# USB.net
KiCad netlist of a schematic drawn in Altium Designer
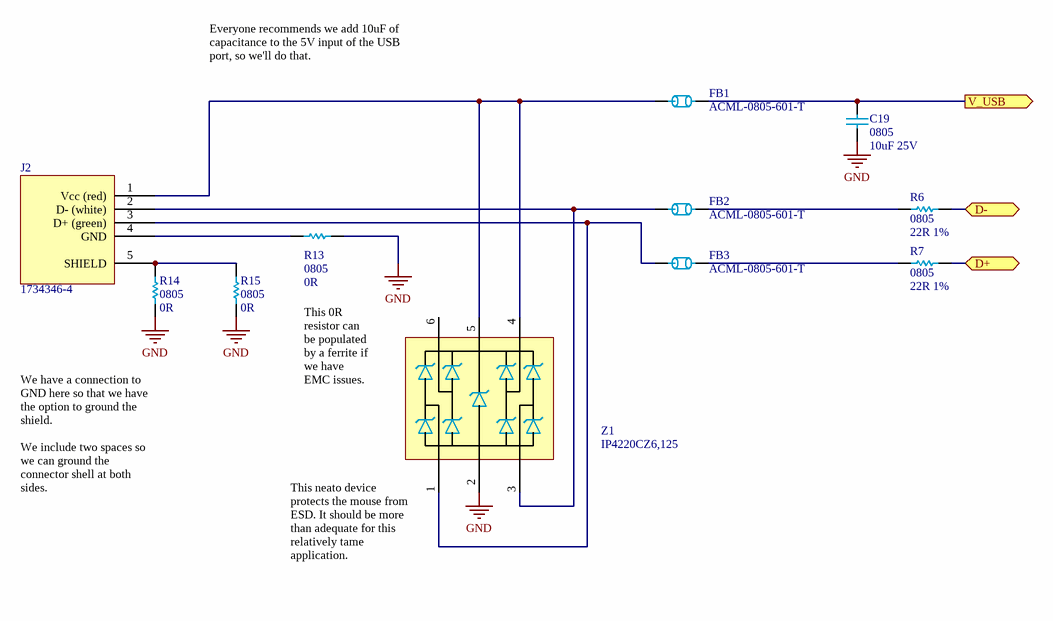
[diagram p0: USB.SchDoc]

(export (version "E")
  (design (tool "Eeschema 10.0.6"))
  (components
    (comp (ref "C19")
      (value "0805")
      (footprint "0805")
      (description "0805, X5R or better")
      (fields (field (name "ALTIUM_VALUE") "10uF 25V"))
      (libsource (lib "Chip_Passives") (part "Cap 10uF 25V"))
    )
    (comp (ref "FB1")
      (value "ACML-0805-601-T")
      (footprint "0805")
      (description "FERRITE BEAD 600 OHM 0805 1LN")
      (libsource (lib "Chip_Passives") (part "ACML-0805-601-T"))
    )
    (comp (ref "FB2")
      (value "ACML-0805-601-T")
      (footprint "0805")
      (description "FERRITE BEAD 600 OHM 0805 1LN")
      (libsource (lib "Chip_Passives") (part "ACML-0805-601-T"))
    )
    (comp (ref "FB3")
      (value "ACML-0805-601-T")
      (footprint "0805")
      (description "FERRITE BEAD 600 OHM 0805 1LN")
      (libsource (lib "Chip_Passives") (part "ACML-0805-601-T"))
    )
    (comp (ref "J2")
      (value "1734346-4")
      (footprint "1734346-4")
      (description "USB - B USB 2.0 Receptacle Connector 4 Position Surface Mount, Right Angle")
      (libsource (lib "Connectors") (part "1734346-4"))
    )
    (comp (ref "R6")
      (value "0805")
      (footprint "0805")
      (description "Chip resistor")
      (fields (field (name "ALTIUM_VALUE") "22R 1%"))
      (libsource (lib "Chip_Passives") (part "Res 22R 1% 0805"))
    )
    (comp (ref "R7")
      (value "0805")
      (footprint "0805")
      (description "Chip resistor")
      (fields (field (name "ALTIUM_VALUE") "22R 1%"))
      (libsource (lib "Chip_Passives") (part "Res 22R 1% 0805"))
    )
    (comp (ref "R13")
      (value "0805")
      (footprint "0805")
      (description "Chip resistor")
      (fields (field (name "ALTIUM_VALUE") "0R"))
      (libsource (lib "Chip_Passives") (part "Res 0R 0805"))
    )
    (comp (ref "R14")
      (value "0805")
      (footprint "0805")
      (description "Chip resistor")
      (fields (field (name "ALTIUM_VALUE") "0R"))
      (libsource (lib "Chip_Passives") (part "Res 0R 0805"))
    )
    (comp (ref "R15")
      (value "0805")
      (footprint "0805")
      (description "Chip resistor")
      (fields (field (name "ALTIUM_VALUE") "0R"))
      (libsource (lib "Chip_Passives") (part "Res 0R 0805"))
    )
    (comp (ref "Z1")
      (value "IP4220CZ6,125")
      (footprint "PESD3V3S4UD - SOT95P275X110-6N")
      (description "TVS DIODE 5.5V 6TSOP (Low capacitance, USB)")
      (libsource (lib "Diodes") (part "IP4220CZ6,125"))
    )
  )
  (nets
    (net (code "1") (name "/D+") (class "Default")
      (node (ref "R7") (pin "2") (pinfunction "2_2") (pintype "passive"))
    )
    (net (code "2") (name "/D-") (class "Default")
      (node (ref "R6") (pin "2") (pinfunction "2_2") (pintype "passive"))
    )
    (net (code "3") (name "/V_USB") (class "Default")
      (node (ref "C19") (pin "2") (pinfunction "2_2") (pintype "passive"))
      (node (ref "FB1") (pin "2") (pinfunction "2_2") (pintype "passive"))
    )
    (net (code "4") (name "GND") (class "Default")
      (node (ref "C19") (pin "1") (pinfunction "1_1") (pintype "passive"))
      (node (ref "R13") (pin "1") (pinfunction "1_1") (pintype "passive"))
      (node (ref "R14") (pin "1") (pinfunction "1_1") (pintype "passive"))
      (node (ref "R15") (pin "1") (pinfunction "1_1") (pintype "passive"))
      (node (ref "Z1") (pin "2") (pinfunction "2_2") (pintype "passive"))
    )
    (net (code "5") (name "Net-(FB2-Pad2)") (class "Default")
      (node (ref "FB2") (pin "2") (pinfunction "2_2") (pintype "passive"))
      (node (ref "R6") (pin "1") (pinfunction "1_1") (pintype "passive"))
    )
    (net (code "6") (name "Net-(FB3-Pad2)") (class "Default")
      (node (ref "FB3") (pin "2") (pinfunction "2_2") (pintype "passive"))
      (node (ref "R7") (pin "1") (pinfunction "1_1") (pintype "passive"))
    )
    (net (code "7") (name "Net-(J2-D+_(green))") (class "Default")
      (node (ref "FB3") (pin "1") (pinfunction "1_1") (pintype "passive"))
      (node (ref "J2") (pin "3") (pinfunction "D+_(green)_3") (pintype "passive"))
      (node (ref "Z1") (pin "1") (pinfunction "1_1") (pintype "passive"))
    )
    (net (code "8") (name "Net-(J2-D-_(white))") (class "Default")
      (node (ref "FB2") (pin "1") (pinfunction "1_1") (pintype "passive"))
      (node (ref "J2") (pin "2") (pinfunction "D-_(white)_2") (pintype "passive"))
      (node (ref "Z1") (pin "3") (pinfunction "3_3") (pintype "passive"))
    )
    (net (code "9") (name "Net-(J2-GND)") (class "Default")
      (node (ref "J2") (pin "4") (pinfunction "GND_4") (pintype "passive"))
      (node (ref "R13") (pin "2") (pinfunction "2_2") (pintype "passive"))
    )
    (net (code "10") (name "Net-(J2-SHIELD)") (class "Default")
      (node (ref "J2") (pin "5") (pinfunction "SHIELD_5") (pintype "passive"))
      (node (ref "R14") (pin "2") (pinfunction "2_2") (pintype "passive"))
      (node (ref "R15") (pin "2") (pinfunction "2_2") (pintype "passive"))
    )
    (net (code "11") (name "Net-(J2-Vcc_(red))") (class "Default")
      (node (ref "FB1") (pin "1") (pinfunction "1_1") (pintype "passive"))
      (node (ref "J2") (pin "1") (pinfunction "Vcc_(red)_1") (pintype "passive"))
      (node (ref "Z1") (pin "4") (pinfunction "4_4") (pintype "passive"))
      (node (ref "Z1") (pin "5") (pinfunction "5_5") (pintype "passive"))
    )
    (net (code "12") (name "unconnected-(Z1-Pad6)") (class "Default")
      (node (ref "Z1") (pin "6") (pinfunction "6_6") (pintype "passive"))
    )
  )
)
